# 780-00057_rev1_Pg2_SCH_NRES_Crate_Slot_M.net
KiCad netlist of a schematic drawn in Altium Designer
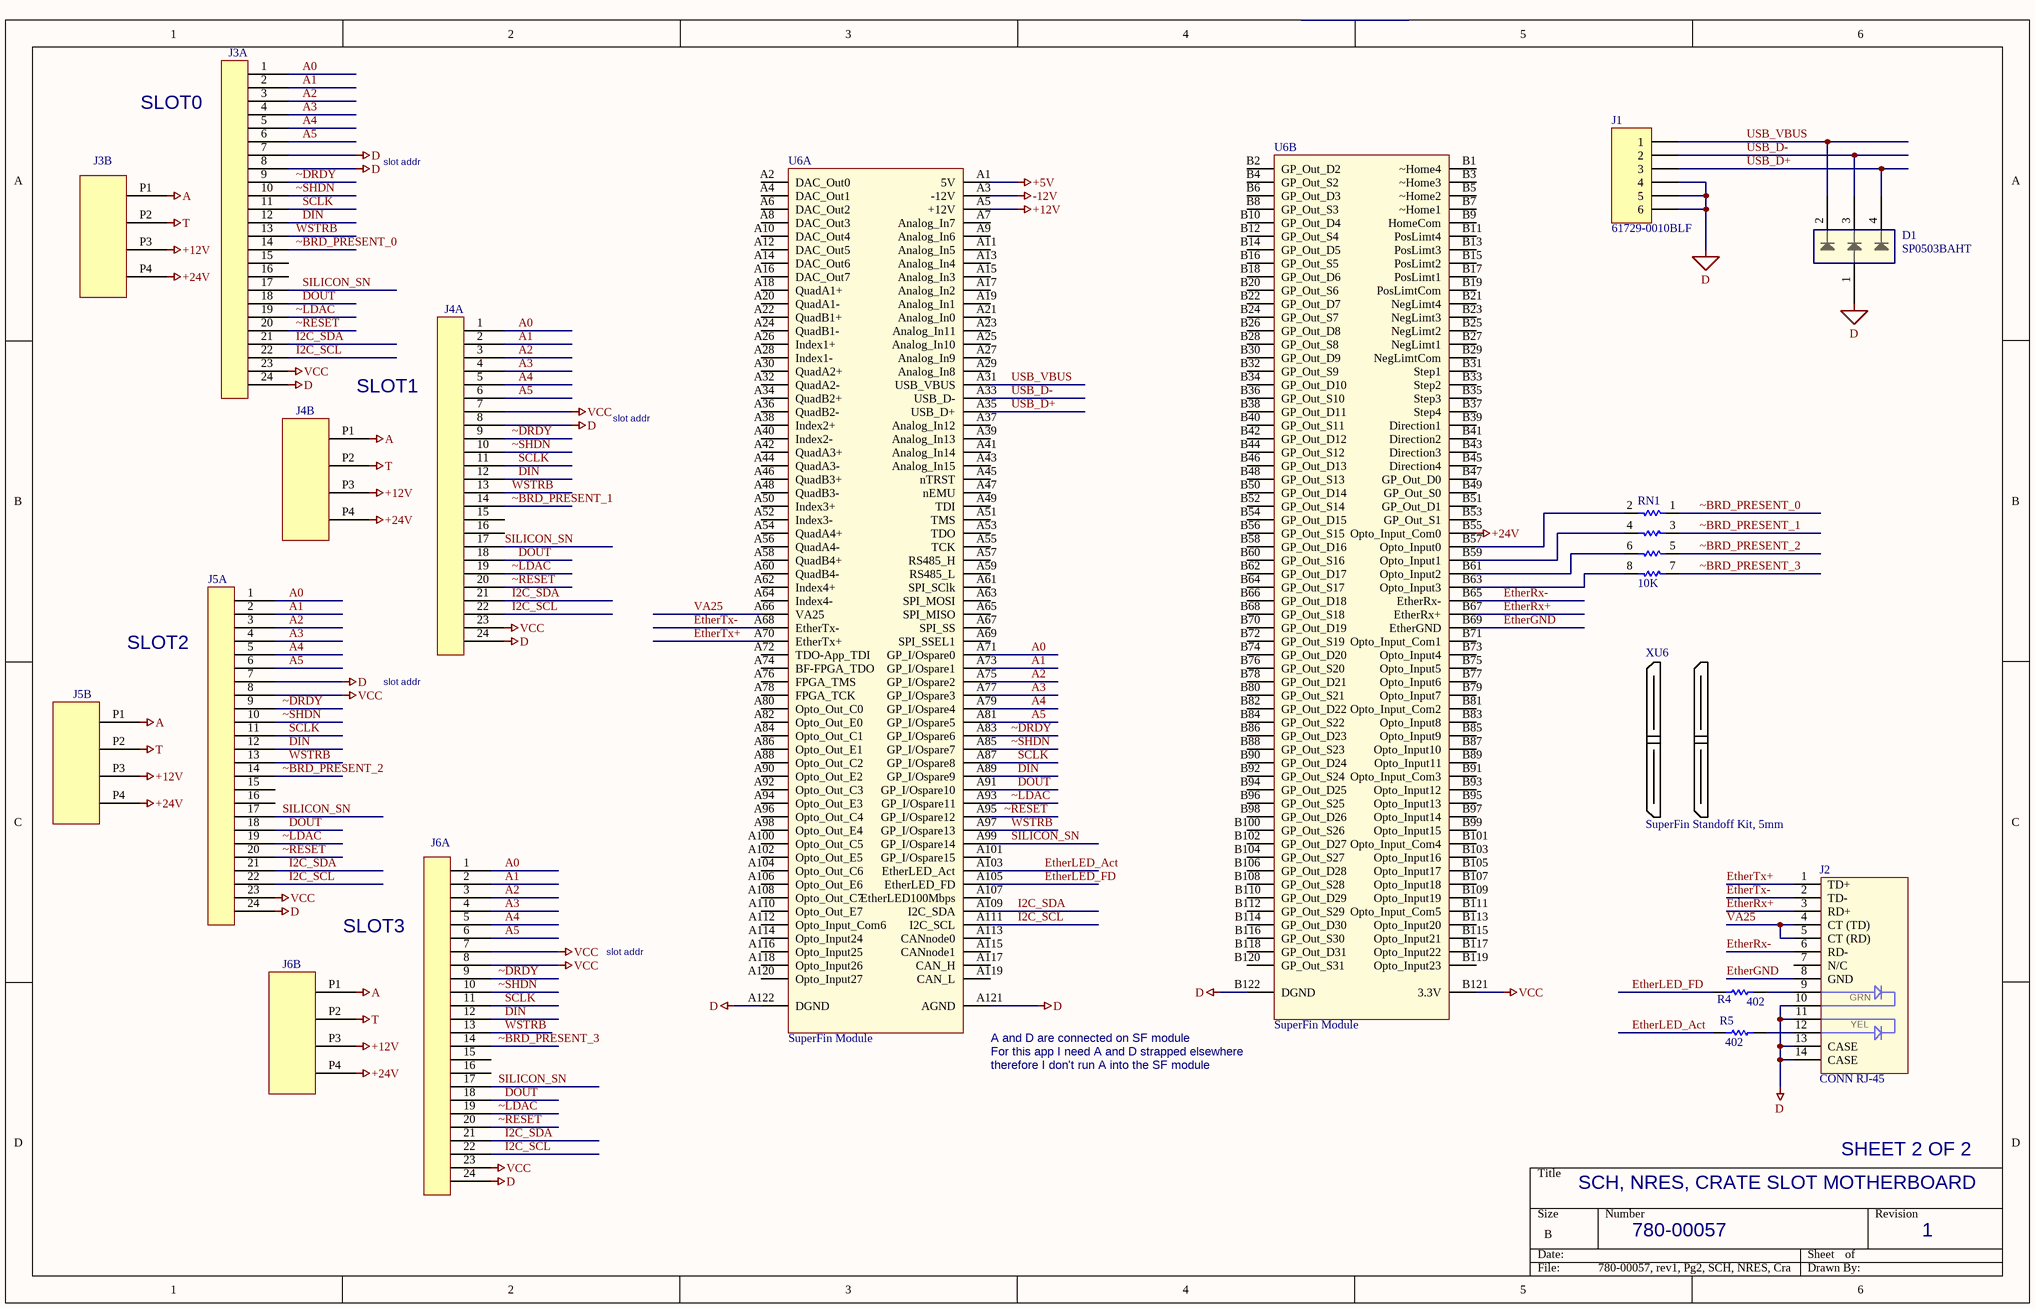
[diagram p0: 780-00057, rev1, Pg2, SCH, NRES, Crate Slot MotherBoard.SchDoc]

(export (version "E")
  (design (tool "Eeschema 10.0.6"))
  (components
    (comp (ref "D1")
      (value "SP0503BAHT")
      (footprint "SOT-143")
      (fields (field (name "MANUFACTURER") "LITTLEFUSE"))
      (libsource (lib "DJAHNG_Library_1") (part "3-Zener"))
    )
    (comp (ref "J1")
      (value "61729-0010BLF")
      (footprint "USB Vertical PCB")
      (description "Header, 6-Pin")
      (fields (field (name "MANUFACTURER") "FCI"))
      (libsource (lib "Miscellaneous Connectors") (part "Header 6"))
    )
    (comp (ref "J2")
      (value "CONN RJ-45")
      (footprint "RJ-45 w/magnetics")
      (description "Right Angle, Standard Profile, RJ45-Keyed, Flange Mount PCB Jack")
      (libsource (lib "Richs Schematic Components") (part "CONN RJ-45 with Magnetics"))
    )
    (comp (ref "J3")
      (value "Molex 46114 backplane connector, 24 signal, 4 pwr")
      (footprint "MOLEX 46114 SERIES")
      (libsource (lib "Richs Schematic Components") (part "Molex 46114 backplane connector, 24 signal, 4 pwr"))
    )
    (comp (ref "J4")
      (value "Molex 46114 backplane connector, 24 signal, 4 pwr")
      (footprint "MOLEX 46114 SERIES")
      (libsource (lib "Richs Schematic Components") (part "Molex 46114 backplane connector, 24 signal, 4 pwr"))
    )
    (comp (ref "J5")
      (value "Molex 46114 backplane connector, 24 signal, 4 pwr")
      (footprint "MOLEX 46114 SERIES")
      (libsource (lib "Richs Schematic Components") (part "Molex 46114 backplane connector, 24 signal, 4 pwr"))
    )
    (comp (ref "J6")
      (value "Molex 46114 backplane connector, 24 signal, 4 pwr")
      (footprint "MOLEX 46114 SERIES")
      (libsource (lib "Richs Schematic Components") (part "Molex 46114 backplane connector, 24 signal, 4 pwr"))
    )
    (comp (ref "R4")
      (value "402")
      (footprint "SMD_0805")
      (description "Resistor 0805")
      (fields (field (name "MANUFACTURER") "Vishay/Dale") (field (name "Comment") "Res 0805"))
      (libsource (lib "Richs Schematic Components") (part "Res SMD"))
    )
    (comp (ref "R5")
      (value "402")
      (footprint "SMD_0805")
      (description "Resistor 0805")
      (fields (field (name "MANUFACTURER") "Vishay/Dale") (field (name "Comment") "Res 0805"))
      (libsource (lib "Richs Schematic Components") (part "Res SMD"))
    )
    (comp (ref "RN1")
      (value "10K")
      (footprint "RES ARRAY 0603 x 4")
      (description "Resistor Array 4 Isolated")
      (fields (field (name "MANUFACTURER") "PANASONIC - ECG") (field (name "Comment") "RES ARRAY  x4 10K"))
      (libsource (lib "Richs Schematic Components") (part "RES ARRAY  x4 10K"))
    )
    (comp (ref "U6")
      (value "SuperFin Module")
      (footprint "SuperFin Footprint")
      (libsource (lib "Richs Schematic Components") (part "SuperFin Module"))
    )
    (comp (ref "XU6")
      (value "SuperFin Standoff Kit, 5mm")
      (libsource (lib "Richs Schematic Components") (part "SuperFin Standoff Kit, 5mm"))
    )
  )
  (nets
    (net (code "1") (name "+5V") (class "Default")
      (node (ref "U6") (pin "A1") (pinfunction "5V_A1") (pintype "passive"))
    )
    (net (code "2") (name "+12V") (class "Default")
      (node (ref "J3") (pin "P3") (pinfunction "S27_P3") (pintype "passive"))
      (node (ref "J4") (pin "P3") (pinfunction "S27_P3") (pintype "passive"))
      (node (ref "J5") (pin "P3") (pinfunction "S27_P3") (pintype "passive"))
      (node (ref "J6") (pin "P3") (pinfunction "S27_P3") (pintype "passive"))
      (node (ref "U6") (pin "A5") (pinfunction "+12V_A5") (pintype "passive"))
    )
    (net (code "3") (name "+24V") (class "Default")
      (node (ref "J3") (pin "P4") (pinfunction "S28_P4") (pintype "passive"))
      (node (ref "J4") (pin "P4") (pinfunction "S28_P4") (pintype "passive"))
      (node (ref "J5") (pin "P4") (pinfunction "S28_P4") (pintype "passive"))
      (node (ref "J6") (pin "P4") (pinfunction "S28_P4") (pintype "passive"))
      (node (ref "U6") (pin "B55") (pinfunction "Opto_Input_Com0_B55") (pintype "passive"))
    )
    (net (code "4") (name "-12V") (class "Default")
      (node (ref "U6") (pin "A3") (pinfunction "-12V_A3") (pintype "passive"))
    )
    (net (code "5") (name "/A0") (class "Default")
      (node (ref "J3") (pin "1") (pintype "passive"))
      (node (ref "J4") (pin "1") (pintype "passive"))
      (node (ref "J5") (pin "1") (pintype "passive"))
      (node (ref "J6") (pin "1") (pintype "passive"))
      (node (ref "U6") (pin "A71") (pinfunction "GP_I/Ospare0_A71") (pintype "passive"))
    )
    (net (code "6") (name "/A1") (class "Default")
      (node (ref "J3") (pin "2") (pintype "passive"))
      (node (ref "J4") (pin "2") (pintype "passive"))
      (node (ref "J5") (pin "2") (pintype "passive"))
      (node (ref "J6") (pin "2") (pintype "passive"))
      (node (ref "U6") (pin "A73") (pinfunction "GP_I/Ospare1_A73") (pintype "passive"))
    )
    (net (code "7") (name "/A2") (class "Default")
      (node (ref "J3") (pin "3") (pintype "passive"))
      (node (ref "J4") (pin "3") (pintype "passive"))
      (node (ref "J5") (pin "3") (pintype "passive"))
      (node (ref "J6") (pin "3") (pintype "passive"))
      (node (ref "U6") (pin "A75") (pinfunction "GP_I/Ospare2_A75") (pintype "passive"))
    )
    (net (code "8") (name "/A3") (class "Default")
      (node (ref "J3") (pin "4") (pintype "passive"))
      (node (ref "J4") (pin "4") (pintype "passive"))
      (node (ref "J5") (pin "4") (pintype "passive"))
      (node (ref "J6") (pin "4") (pintype "passive"))
      (node (ref "U6") (pin "A77") (pinfunction "GP_I/Ospare3_A77") (pintype "passive"))
    )
    (net (code "9") (name "/A4") (class "Default")
      (node (ref "J3") (pin "5") (pintype "passive"))
      (node (ref "J4") (pin "5") (pintype "passive"))
      (node (ref "J5") (pin "5") (pintype "passive"))
      (node (ref "J6") (pin "5") (pintype "passive"))
      (node (ref "U6") (pin "A79") (pinfunction "GP_I/Ospare4_A79") (pintype "passive"))
    )
    (net (code "10") (name "/A5") (class "Default")
      (node (ref "J3") (pin "6") (pintype "passive"))
      (node (ref "J4") (pin "6") (pintype "passive"))
      (node (ref "J5") (pin "6") (pintype "passive"))
      (node (ref "J6") (pin "6") (pintype "passive"))
      (node (ref "U6") (pin "A81") (pinfunction "GP_I/Ospare5_A81") (pintype "passive"))
    )
    (net (code "11") (name "/DIN") (class "Default")
      (node (ref "J3") (pin "12") (pintype "passive"))
      (node (ref "J4") (pin "12") (pintype "passive"))
      (node (ref "J5") (pin "12") (pintype "passive"))
      (node (ref "J6") (pin "12") (pintype "passive"))
      (node (ref "U6") (pin "A89") (pinfunction "GP_I/Ospare9_A89") (pintype "passive"))
    )
    (net (code "12") (name "/DOUT") (class "Default")
      (node (ref "J3") (pin "18") (pintype "passive"))
      (node (ref "J4") (pin "18") (pintype "passive"))
      (node (ref "J5") (pin "18") (pintype "passive"))
      (node (ref "J6") (pin "18") (pintype "passive"))
      (node (ref "U6") (pin "A91") (pinfunction "GP_I/Ospare10_A91") (pintype "passive"))
    )
    (net (code "13") (name "/EtherGND") (class "Default")
      (node (ref "J2") (pin "8") (pinfunction "GND_8") (pintype "passive"))
      (node (ref "U6") (pin "B69") (pinfunction "EtherGND_B69") (pintype "passive"))
    )
    (net (code "14") (name "/EtherLED_Act") (class "Default")
      (node (ref "R5") (pin "1") (pinfunction "1_1") (pintype "passive"))
      (node (ref "U6") (pin "A103") (pinfunction "EtherLED_Act_A103") (pintype "passive"))
    )
    (net (code "15") (name "/EtherLED_FD") (class "Default")
      (node (ref "R4") (pin "1") (pinfunction "1_1") (pintype "passive"))
      (node (ref "U6") (pin "A105") (pinfunction "EtherLED_FD_A105") (pintype "passive"))
    )
    (net (code "16") (name "/EtherRx+") (class "Default")
      (node (ref "J2") (pin "3") (pinfunction "RD+_3") (pintype "passive"))
      (node (ref "U6") (pin "B67") (pinfunction "EtherRx+_B67") (pintype "passive"))
    )
    (net (code "17") (name "/EtherRx-") (class "Default")
      (node (ref "J2") (pin "6") (pinfunction "RD-_6") (pintype "passive"))
      (node (ref "U6") (pin "B65") (pinfunction "EtherRx-_B65") (pintype "passive"))
    )
    (net (code "18") (name "/EtherTx+") (class "Default")
      (node (ref "J2") (pin "1") (pinfunction "TD+_1") (pintype "passive"))
      (node (ref "U6") (pin "A70") (pinfunction "EtherTx+_A70") (pintype "passive"))
    )
    (net (code "19") (name "/EtherTx-") (class "Default")
      (node (ref "J2") (pin "2") (pinfunction "TD-_2") (pintype "passive"))
      (node (ref "U6") (pin "A68") (pinfunction "EtherTx-_A68") (pintype "passive"))
    )
    (net (code "20") (name "/I2C_SCL") (class "Default")
      (node (ref "J3") (pin "22") (pintype "passive"))
      (node (ref "J4") (pin "22") (pintype "passive"))
      (node (ref "J5") (pin "22") (pintype "passive"))
      (node (ref "J6") (pin "22") (pintype "passive"))
      (node (ref "U6") (pin "A111") (pinfunction "I2C_SCL_A111") (pintype "passive"))
    )
    (net (code "21") (name "/I2C_SDA") (class "Default")
      (node (ref "J3") (pin "21") (pintype "passive"))
      (node (ref "J4") (pin "21") (pintype "passive"))
      (node (ref "J5") (pin "21") (pintype "passive"))
      (node (ref "J6") (pin "21") (pintype "passive"))
      (node (ref "U6") (pin "A109") (pinfunction "I2C_SDA_A109") (pintype "passive"))
    )
    (net (code "22") (name "/SCLK") (class "Default")
      (node (ref "J3") (pin "11") (pintype "passive"))
      (node (ref "J4") (pin "11") (pintype "passive"))
      (node (ref "J5") (pin "11") (pintype "passive"))
      (node (ref "J6") (pin "11") (pintype "passive"))
      (node (ref "U6") (pin "A87") (pinfunction "GP_I/Ospare8_A87") (pintype "passive"))
    )
    (net (code "23") (name "/SILICON_SN") (class "Default")
      (node (ref "J3") (pin "17") (pintype "passive"))
      (node (ref "J4") (pin "17") (pintype "passive"))
      (node (ref "J5") (pin "17") (pintype "passive"))
      (node (ref "J6") (pin "17") (pintype "passive"))
      (node (ref "U6") (pin "A99") (pinfunction "GP_I/Ospare14_A99") (pintype "passive"))
    )
    (net (code "24") (name "/USB_D+") (class "Default")
      (node (ref "D1") (pin "4") (pinfunction "K3_4") (pintype "passive"))
      (node (ref "J1") (pin "3") (pinfunction "3_3") (pintype "passive"))
      (node (ref "U6") (pin "A35") (pinfunction "USB_D+_A35") (pintype "passive"))
    )
    (net (code "25") (name "/USB_D-") (class "Default")
      (node (ref "D1") (pin "3") (pinfunction "K2_3") (pintype "passive"))
      (node (ref "J1") (pin "2") (pinfunction "2_2") (pintype "passive"))
      (node (ref "U6") (pin "A33") (pinfunction "USB_D-_A33") (pintype "passive"))
    )
    (net (code "26") (name "/USB_VBUS") (class "Default")
      (node (ref "D1") (pin "2") (pinfunction "K1_2") (pintype "passive"))
      (node (ref "J1") (pin "1") (pinfunction "1_1") (pintype "passive"))
      (node (ref "U6") (pin "A31") (pinfunction "USB_VBUS_A31") (pintype "passive"))
    )
    (net (code "27") (name "/VA25") (class "Default")
      (node (ref "J2") (pin "4") (pinfunction "CT_(TD)_4") (pintype "passive"))
      (node (ref "J2") (pin "5") (pinfunction "CT_(RD)_5") (pintype "passive"))
      (node (ref "U6") (pin "A66") (pinfunction "VA25_A66") (pintype "passive"))
    )
    (net (code "28") (name "/WSTRB") (class "Default")
      (node (ref "J3") (pin "13") (pintype "passive"))
      (node (ref "J4") (pin "13") (pintype "passive"))
      (node (ref "J5") (pin "13") (pintype "passive"))
      (node (ref "J6") (pin "13") (pintype "passive"))
      (node (ref "U6") (pin "A97") (pinfunction "GP_I/Ospare13_A97") (pintype "passive"))
    )
    (net (code "29") (name "/~BRD_PRESENT_0") (class "Default")
      (node (ref "J3") (pin "14") (pintype "passive"))
      (node (ref "RN1") (pin "1") (pinfunction "1_1") (pintype "passive"))
    )
    (net (code "30") (name "/~BRD_PRESENT_1") (class "Default")
      (node (ref "J4") (pin "14") (pintype "passive"))
      (node (ref "RN1") (pin "3") (pinfunction "3_3") (pintype "passive"))
    )
    (net (code "31") (name "/~BRD_PRESENT_2") (class "Default")
      (node (ref "J5") (pin "14") (pintype "passive"))
      (node (ref "RN1") (pin "5") (pinfunction "5_5") (pintype "passive"))
    )
    (net (code "32") (name "/~BRD_PRESENT_3") (class "Default")
      (node (ref "J6") (pin "14") (pintype "passive"))
      (node (ref "RN1") (pin "7") (pinfunction "1_7") (pintype "passive"))
    )
    (net (code "33") (name "/~DRDY") (class "Default")
      (node (ref "J3") (pin "9") (pintype "passive"))
      (node (ref "J4") (pin "9") (pintype "passive"))
      (node (ref "J5") (pin "9") (pintype "passive"))
      (node (ref "J6") (pin "9") (pintype "passive"))
      (node (ref "U6") (pin "A83") (pinfunction "GP_I/Ospare6_A83") (pintype "passive"))
    )
    (net (code "34") (name "/~LDAC") (class "Default")
      (node (ref "J3") (pin "19") (pintype "passive"))
      (node (ref "J4") (pin "19") (pintype "passive"))
      (node (ref "J5") (pin "19") (pintype "passive"))
      (node (ref "J6") (pin "19") (pintype "passive"))
      (node (ref "U6") (pin "A93") (pinfunction "GP_I/Ospare11_A93") (pintype "passive"))
    )
    (net (code "35") (name "/~RESET") (class "Default")
      (node (ref "J3") (pin "20") (pintype "passive"))
      (node (ref "J4") (pin "20") (pintype "passive"))
      (node (ref "J5") (pin "20") (pintype "passive"))
      (node (ref "J6") (pin "20") (pintype "passive"))
      (node (ref "U6") (pin "A95") (pinfunction "GP_I/Ospare12_A95") (pintype "passive"))
    )
    (net (code "36") (name "/~SHDN") (class "Default")
      (node (ref "J3") (pin "10") (pintype "passive"))
      (node (ref "J4") (pin "10") (pintype "passive"))
      (node (ref "J5") (pin "10") (pintype "passive"))
      (node (ref "J6") (pin "10") (pintype "passive"))
      (node (ref "U6") (pin "A85") (pinfunction "GP_I/Ospare7_A85") (pintype "passive"))
    )
    (net (code "37") (name "A") (class "Default")
      (node (ref "J3") (pin "P1") (pinfunction "S25_P1") (pintype "passive"))
      (node (ref "J4") (pin "P1") (pinfunction "S25_P1") (pintype "passive"))
      (node (ref "J5") (pin "P1") (pinfunction "S25_P1") (pintype "passive"))
      (node (ref "J6") (pin "P1") (pinfunction "S25_P1") (pintype "passive"))
    )
    (net (code "38") (name "D") (class "Default")
      (node (ref "D1") (pin "1") (pinfunction "A_1") (pintype "passive"))
      (node (ref "J1") (pin "4") (pinfunction "4_4") (pintype "passive"))
      (node (ref "J1") (pin "5") (pinfunction "5_5") (pintype "passive"))
      (node (ref "J1") (pin "6") (pinfunction "6_6") (pintype "passive"))
      (node (ref "J2") (pin "10") (pinfunction "GRN-Cathode_10") (pintype "passive"))
      (node (ref "J2") (pin "11") (pinfunction "YEL-Cathode_11") (pintype "passive"))
      (node (ref "J2") (pin "13") (pinfunction "CASE_13") (pintype "passive"))
      (node (ref "J2") (pin "14") (pinfunction "CASE_14") (pintype "passive"))
      (node (ref "J3") (pin "24") (pintype "passive"))
      (node (ref "J3") (pin "7") (pintype "passive"))
      (node (ref "J3") (pin "8") (pintype "passive"))
      (node (ref "J4") (pin "24") (pintype "passive"))
      (node (ref "J4") (pin "8") (pintype "passive"))
      (node (ref "J5") (pin "24") (pintype "passive"))
      (node (ref "J5") (pin "7") (pintype "passive"))
      (node (ref "J6") (pin "24") (pintype "passive"))
      (node (ref "U6") (pin "A121") (pinfunction "AGND_A121") (pintype "passive"))
      (node (ref "U6") (pin "A122") (pinfunction "DGND_A122") (pintype "passive"))
      (node (ref "U6") (pin "B122") (pinfunction "DGND_B122") (pintype "passive"))
    )
    (net (code "39") (name "Net-(J2-GRN-Anode)") (class "Default")
      (node (ref "J2") (pin "9") (pinfunction "GRN-Anode_9") (pintype "passive"))
      (node (ref "R4") (pin "2") (pinfunction "2_2") (pintype "passive"))
    )
    (net (code "40") (name "Net-(J2-YEL-Anode)") (class "Default")
      (node (ref "J2") (pin "12") (pinfunction "YEL-Anode_12") (pintype "passive"))
      (node (ref "R5") (pin "2") (pinfunction "2_2") (pintype "passive"))
    )
    (net (code "41") (name "Net-(U6B-Opto_Input0)") (class "Default")
      (node (ref "RN1") (pin "2") (pinfunction "2_2") (pintype "passive"))
      (node (ref "U6") (pin "B57") (pinfunction "Opto_Input0_B57") (pintype "passive"))
    )
    (net (code "42") (name "Net-(U6B-Opto_Input1)") (class "Default")
      (node (ref "RN1") (pin "4") (pinfunction "4_4") (pintype "passive"))
      (node (ref "U6") (pin "B59") (pinfunction "Opto_Input1_B59") (pintype "passive"))
    )
    (net (code "43") (name "Net-(U6B-Opto_Input2)") (class "Default")
      (node (ref "RN1") (pin "6") (pinfunction "6_6") (pintype "passive"))
      (node (ref "U6") (pin "B61") (pinfunction "Opto_Input2_B61") (pintype "passive"))
    )
    (net (code "44") (name "Net-(U6B-Opto_Input3)") (class "Default")
      (node (ref "RN1") (pin "8") (pinfunction "8_8") (pintype "passive"))
      (node (ref "U6") (pin "B63") (pinfunction "Opto_Input3_B63") (pintype "passive"))
    )
    (net (code "45") (name "T") (class "Default")
      (node (ref "J3") (pin "P2") (pinfunction "S26_P2") (pintype "passive"))
      (node (ref "J4") (pin "P2") (pinfunction "S26_P2") (pintype "passive"))
      (node (ref "J5") (pin "P2") (pinfunction "S26_P2") (pintype "passive"))
      (node (ref "J6") (pin "P2") (pinfunction "S26_P2") (pintype "passive"))
    )
    (net (code "46") (name "VCC") (class "Default")
      (node (ref "J3") (pin "23") (pintype "passive"))
      (node (ref "J4") (pin "23") (pintype "passive"))
      (node (ref "J4") (pin "7") (pintype "passive"))
      (node (ref "J5") (pin "23") (pintype "passive"))
      (node (ref "J5") (pin "8") (pintype "passive"))
      (node (ref "J6") (pin "23") (pintype "passive"))
      (node (ref "J6") (pin "7") (pintype "passive"))
      (node (ref "J6") (pin "8") (pintype "passive"))
      (node (ref "U6") (pin "B121") (pinfunction "3.3V_B121") (pintype "passive"))
    )
    (net (code "47") (name "unconnected-(J2-N{slash}C-Pad7)") (class "Default")
      (node (ref "J2") (pin "7") (pinfunction "N/C_7") (pintype "passive"))
    )
    (net (code "48") (name "unconnected-(J3-Pad15)") (class "Default")
      (node (ref "J3") (pin "15") (pintype "passive"))
    )
    (net (code "49") (name "unconnected-(J3-Pad16)") (class "Default")
      (node (ref "J3") (pin "16") (pintype "passive"))
    )
    (net (code "50") (name "unconnected-(J4-Pad15)") (class "Default")
      (node (ref "J4") (pin "15") (pintype "passive"))
    )
    (net (code "51") (name "unconnected-(J4-Pad16)") (class "Default")
      (node (ref "J4") (pin "16") (pintype "passive"))
    )
    (net (code "52") (name "unconnected-(J5-Pad15)") (class "Default")
      (node (ref "J5") (pin "15") (pintype "passive"))
    )
    (net (code "53") (name "unconnected-(J5-Pad16)") (class "Default")
      (node (ref "J5") (pin "16") (pintype "passive"))
    )
    (net (code "54") (name "unconnected-(J6-Pad15)") (class "Default")
      (node (ref "J6") (pin "15") (pintype "passive"))
    )
    (net (code "55") (name "unconnected-(J6-Pad16)") (class "Default")
      (node (ref "J6") (pin "16") (pintype "passive"))
    )
    (net (code "56") (name "unconnected-(U6A-Analog_In0-PadA21)") (class "Default")
      (node (ref "U6") (pin "A21") (pinfunction "Analog_In0_A21") (pintype "passive"))
    )
    (net (code "57") (name "unconnected-(U6A-Analog_In1-PadA19)") (class "Default")
      (node (ref "U6") (pin "A19") (pinfunction "Analog_In1_A19") (pintype "passive"))
    )
    (net (code "58") (name "unconnected-(U6A-Analog_In2-PadA17)") (class "Default")
      (node (ref "U6") (pin "A17") (pinfunction "Analog_In2_A17") (pintype "passive"))
    )
    (net (code "59") (name "unconnected-(U6A-Analog_In3-PadA15)") (class "Default")
      (node (ref "U6") (pin "A15") (pinfunction "Analog_In3_A15") (pintype "passive"))
    )
    (net (code "60") (name "unconnected-(U6A-Analog_In4-PadA13)") (class "Default")
      (node (ref "U6") (pin "A13") (pinfunction "Analog_In4_A13") (pintype "passive"))
    )
    (net (code "61") (name "unconnected-(U6A-Analog_In5-PadA11)") (class "Default")
      (node (ref "U6") (pin "A11") (pinfunction "Analog_In5_A11") (pintype "passive"))
    )
    (net (code "62") (name "unconnected-(U6A-Analog_In6-PadA9)") (class "Default")
      (node (ref "U6") (pin "A9") (pinfunction "Analog_In6_A9") (pintype "passive"))
    )
    (net (code "63") (name "unconnected-(U6A-Analog_In7-PadA7)") (class "Default")
      (node (ref "U6") (pin "A7") (pinfunction "Analog_In7_A7") (pintype "passive"))
    )
    (net (code "64") (name "unconnected-(U6A-Analog_In8-PadA29)") (class "Default")
      (node (ref "U6") (pin "A29") (pinfunction "Analog_In8_A29") (pintype "passive"))
    )
    (net (code "65") (name "unconnected-(U6A-Analog_In9-PadA27)") (class "Default")
      (node (ref "U6") (pin "A27") (pinfunction "Analog_In9_A27") (pintype "passive"))
    )
    (net (code "66") (name "unconnected-(U6A-Analog_In10-PadA25)") (class "Default")
      (node (ref "U6") (pin "A25") (pinfunction "Analog_In10_A25") (pintype "passive"))
    )
    (net (code "67") (name "unconnected-(U6A-Analog_In11-PadA23)") (class "Default")
      (node (ref "U6") (pin "A23") (pinfunction "Analog_In11_A23") (pintype "passive"))
    )
    (net (code "68") (name "unconnected-(U6A-Analog_In12-PadA37)") (class "Default")
      (node (ref "U6") (pin "A37") (pinfunction "Analog_In12_A37") (pintype "passive"))
    )
    (net (code "69") (name "unconnected-(U6A-Analog_In13-PadA39)") (class "Default")
      (node (ref "U6") (pin "A39") (pinfunction "Analog_In13_A39") (pintype "passive"))
    )
    (net (code "70") (name "unconnected-(U6A-Analog_In14-PadA41)") (class "Default")
      (node (ref "U6") (pin "A41") (pinfunction "Analog_In14_A41") (pintype "passive"))
    )
    (net (code "71") (name "unconnected-(U6A-Analog_In15-PadA43)") (class "Default")
      (node (ref "U6") (pin "A43") (pinfunction "Analog_In15_A43") (pintype "passive"))
    )
    (net (code "72") (name "unconnected-(U6A-BF-FPGA_TDO-PadA74)") (class "Default")
      (node (ref "U6") (pin "A74") (pinfunction "BF-FPGA_TDO_A74") (pintype "passive"))
    )
    (net (code "73") (name "unconnected-(U6A-CAN_H-PadA117)") (class "Default")
      (node (ref "U6") (pin "A117") (pinfunction "CAN_H_A117") (pintype "passive"))
    )
    (net (code "74") (name "unconnected-(U6A-CAN_L-PadA119)") (class "Default")
      (node (ref "U6") (pin "A119") (pinfunction "CAN_L_A119") (pintype "passive"))
    )
    (net (code "75") (name "unconnected-(U6A-CANnode0-PadA113)") (class "Default")
      (node (ref "U6") (pin "A113") (pinfunction "CANnode0_A113") (pintype "passive"))
    )
    (net (code "76") (name "unconnected-(U6A-CANnode1-PadA115)") (class "Default")
      (node (ref "U6") (pin "A115") (pinfunction "CANnode1_A115") (pintype "passive"))
    )
    (net (code "77") (name "unconnected-(U6A-DAC_Out0-PadA2)") (class "Default")
      (node (ref "U6") (pin "A2") (pinfunction "DAC_Out0_A2") (pintype "passive"))
    )
    (net (code "78") (name "unconnected-(U6A-DAC_Out1-PadA4)") (class "Default")
      (node (ref "U6") (pin "A4") (pinfunction "DAC_Out1_A4") (pintype "passive"))
    )
    (net (code "79") (name "unconnected-(U6A-DAC_Out2-PadA6)") (class "Default")
      (node (ref "U6") (pin "A6") (pinfunction "DAC_Out2_A6") (pintype "passive"))
    )
    (net (code "80") (name "unconnected-(U6A-DAC_Out3-PadA8)") (class "Default")
      (node (ref "U6") (pin "A8") (pinfunction "DAC_Out3_A8") (pintype "passive"))
    )
    (net (code "81") (name "unconnected-(U6A-DAC_Out4-PadA10)") (class "Default")
      (node (ref "U6") (pin "A10") (pinfunction "DAC_Out4_A10") (pintype "passive"))
    )
    (net (code "82") (name "unconnected-(U6A-DAC_Out5-PadA12)") (class "Default")
      (node (ref "U6") (pin "A12") (pinfunction "DAC_Out5_A12") (pintype "passive"))
    )
    (net (code "83") (name "unconnected-(U6A-DAC_Out6-PadA14)") (class "Default")
      (node (ref "U6") (pin "A14") (pinfunction "DAC_Out6_A14") (pintype "passive"))
    )
    (net (code "84") (name "unconnected-(U6A-DAC_Out7-PadA16)") (class "Default")
      (node (ref "U6") (pin "A16") (pinfunction "DAC_Out7_A16") (pintype "passive"))
    )
    (net (code "85") (name "unconnected-(U6A-EtherLED100Mbps-PadA107)") (class "Default")
      (node (ref "U6") (pin "A107") (pinfunction "EtherLED100Mbps_A107") (pintype "passive"))
    )
    (net (code "86") (name "unconnected-(U6A-FPGA_TCK-PadA78)") (class "Default")
      (node (ref "U6") (pin "A78") (pinfunction "FPGA_TCK_A78") (pintype "passive"))
    )
    (net (code "87") (name "unconnected-(U6A-FPGA_TMS-PadA76)") (class "Default")
      (node (ref "U6") (pin "A76") (pinfunction "FPGA_TMS_A76") (pintype "passive"))
    )
    (net (code "88") (name "unconnected-(U6A-GP_I{slash}Ospare15-PadA101)") (class "Default")
      (node (ref "U6") (pin "A101") (pinfunction "GP_I/Ospare15_A101") (pintype "passive"))
    )
    (net (code "89") (name "unconnected-(U6A-Index1+-PadA26)") (class "Default")
      (node (ref "U6") (pin "A26") (pinfunction "Index1+_A26") (pintype "passive"))
    )
    (net (code "90") (name "unconnected-(U6A-Index1--PadA28)") (class "Default")
      (node (ref "U6") (pin "A28") (pinfunction "Index1-_A28") (pintype "passive"))
    )
    (net (code "91") (name "unconnected-(U6A-Index2+-PadA38)") (class "Default")
      (node (ref "U6") (pin "A38") (pinfunction "Index2+_A38") (pintype "passive"))
    )
    (net (code "92") (name "unconnected-(U6A-Index2--PadA40)") (class "Default")
      (node (ref "U6") (pin "A40") (pinfunction "Index2-_A40") (pintype "passive"))
    )
    (net (code "93") (name "unconnected-(U6A-Index3+-PadA50)") (class "Default")
      (node (ref "U6") (pin "A50") (pinfunction "Index3+_A50") (pintype "passive"))
    )
    (net (code "94") (name "unconnected-(U6A-Index3--PadA52)") (class "Default")
      (node (ref "U6") (pin "A52") (pinfunction "Index3-_A52") (pintype "passive"))
    )
    (net (code "95") (name "unconnected-(U6A-Index4+-PadA62)") (class "Default")
      (node (ref "U6") (pin "A62") (pinfunction "Index4+_A62") (pintype "passive"))
    )
    (net (code "96") (name "unconnected-(U6A-Index4--PadA64)") (class "Default")
      (node (ref "U6") (pin "A64") (pinfunction "Index4-_A64") (pintype "passive"))
    )
    (net (code "97") (name "unconnected-(U6A-Opto_Input24-PadA114)") (class "Default")
      (node (ref "U6") (pin "A114") (pinfunction "Opto_Input24_A114") (pintype "passive"))
    )
    (net (code "98") (name "unconnected-(U6A-Opto_Input25-PadA116)") (class "Default")
      (node (ref "U6") (pin "A116") (pinfunction "Opto_Input25_A116") (pintype "passive"))
    )
    (net (code "99") (name "unconnected-(U6A-Opto_Input26-PadA118)") (class "Default")
      (node (ref "U6") (pin "A118") (pinfunction "Opto_Input26_A118") (pintype "passive"))
    )
    (net (code "100") (name "unconnected-(U6A-Opto_Input27-PadA120)") (class "Default")
      (node (ref "U6") (pin "A120") (pinfunction "Opto_Input27_A120") (pintype "passive"))
    )
    (net (code "101") (name "unconnected-(U6A-Opto_Input_Com6-PadA112)") (class "Default")
      (node (ref "U6") (pin "A112") (pinfunction "Opto_Input_Com6_A112") (pintype "passive"))
    )
    (net (code "102") (name "unconnected-(U6A-Opto_Out_C0-PadA80)") (class "Default")
      (node (ref "U6") (pin "A80") (pinfunction "Opto_Out_C0_A80") (pintype "passive"))
    )
    (net (code "103") (name "unconnected-(U6A-Opto_Out_C1-PadA84)") (class "Default")
      (node (ref "U6") (pin "A84") (pinfunction "Opto_Out_C1_A84") (pintype "passive"))
    )
    (net (code "104") (name "unconnected-(U6A-Opto_Out_C2-PadA88)") (class "Default")
      (node (ref "U6") (pin "A88") (pinfunction "Opto_Out_C2_A88") (pintype "passive"))
    )
    (net (code "105") (name "unconnected-(U6A-Opto_Out_C3-PadA92)") (class "Default")
      (node (ref "U6") (pin "A92") (pinfunction "Opto_Out_C3_A92") (pintype "passive"))
    )
    (net (code "106") (name "unconnected-(U6A-Opto_Out_C4-PadA96)") (class "Default")
      (node (ref "U6") (pin "A96") (pinfunction "Opto_Out_C4_A96") (pintype "passive"))
    )
    (net (code "107") (name "unconnected-(U6A-Opto_Out_C5-PadA100)") (class "Default")
      (node (ref "U6") (pin "A100") (pinfunction "Opto_Out_C5_A100") (pintype "passive"))
    )
    (net (code "108") (name "unconnected-(U6A-Opto_Out_C6-PadA104)") (class "Default")
      (node (ref "U6") (pin "A104") (pinfunction "Opto_Out_C6_A104") (pintype "passive"))
    )
    (net (code "109") (name "unconnected-(U6A-Opto_Out_C7-PadA108)") (class "Default")
      (node (ref "U6") (pin "A108") (pinfunction "Opto_Out_C7_A108") (pintype "passive"))
    )
    (net (code "110") (name "unconnected-(U6A-Opto_Out_E0-PadA82)") (class "Default")
      (node (ref "U6") (pin "A82") (pinfunction "Opto_Out_E0_A82") (pintype "passive"))
    )
    (net (code "111") (name "unconnected-(U6A-Opto_Out_E1-PadA86)") (class "Default")
      (node (ref "U6") (pin "A86") (pinfunction "Opto_Out_E1_A86") (pintype "passive"))
    )
    (net (code "112") (name "unconnected-(U6A-Opto_Out_E2-PadA90)") (class "Default")
      (node (ref "U6") (pin "A90") (pinfunction "Opto_Out_E2_A90") (pintype "passive"))
    )
    (net (code "113") (name "unconnected-(U6A-Opto_Out_E3-PadA94)") (class "Default")
      (node (ref "U6") (pin "A94") (pinfunction "Opto_Out_E3_A94") (pintype "passive"))
    )
    (net (code "114") (name "unconnected-(U6A-Opto_Out_E4-PadA98)") (class "Default")
      (node (ref "U6") (pin "A98") (pinfunction "Opto_Out_E4_A98") (pintype "passive"))
    )
    (net (code "115") (name "unconnected-(U6A-Opto_Out_E5-PadA102)") (class "Default")
      (node (ref "U6") (pin "A102") (pinfunction "Opto_Out_E5_A102") (pintype "passive"))
    )
    (net (code "116") (name "unconnected-(U6A-Opto_Out_E6-PadA106)") (class "Default")
      (node (ref "U6") (pin "A106") (pinfunction "Opto_Out_E6_A106") (pintype "passive"))
    )
    (net (code "117") (name "unconnected-(U6A-Opto_Out_E7-PadA110)") (class "Default")
      (node (ref "U6") (pin "A110") (pinfunction "Opto_Out_E7_A110") (pintype "passive"))
    )
    (net (code "118") (name "unconnected-(U6A-QuadA1+-PadA18)") (class "Default")
      (node (ref "U6") (pin "A18") (pinfunction "QuadA1+_A18") (pintype "passive"))
    )
    (net (code "119") (name "unconnected-(U6A-QuadA1--PadA20)") (class "Default")
      (node (ref "U6") (pin "A20") (pinfunction "QuadA1-_A20") (pintype "passive"))
    )
    (net (code "120") (name "unconnected-(U6A-QuadA2+-PadA30)") (class "Default")
      (node (ref "U6") (pin "A30") (pinfunction "QuadA2+_A30") (pintype "passive"))
    )
    (net (code "121") (name "unconnected-(U6A-QuadA2--PadA32)") (class "Default")
      (node (ref "U6") (pin "A32") (pinfunction "QuadA2-_A32") (pintype "passive"))
    )
    (net (code "122") (name "unconnected-(U6A-QuadA3+-PadA42)") (class "Default")
      (node (ref "U6") (pin "A42") (pinfunction "QuadA3+_A42") (pintype "passive"))
    )
    (net (code "123") (name "unconnected-(U6A-QuadA3--PadA44)") (class "Default")
      (node (ref "U6") (pin "A44") (pinfunction "QuadA3-_A44") (pintype "passive"))
    )
    (net (code "124") (name "unconnected-(U6A-QuadA4+-PadA54)") (class "Default")
      (node (ref "U6") (pin "A54") (pinfunction "QuadA4+_A54") (pintype "passive"))
    )
    (net (code "125") (name "unconnected-(U6A-QuadA4--PadA56)") (class "Default")
      (node (ref "U6") (pin "A56") (pinfunction "QuadA4-_A56") (pintype "passive"))
    )
    (net (code "126") (name "unconnected-(U6A-QuadB1+-PadA22)") (class "Default")
      (node (ref "U6") (pin "A22") (pinfunction "QuadB1+_A22") (pintype "passive"))
    )
    (net (code "127") (name "unconnected-(U6A-QuadB1--PadA24)") (class "Default")
      (node (ref "U6") (pin "A24") (pinfunction "QuadB1-_A24") (pintype "passive"))
    )
    (net (code "128") (name "unconnected-(U6A-QuadB2+-PadA34)") (class "Default")
      (node (ref "U6") (pin "A34") (pinfunction "QuadB2+_A34") (pintype "passive"))
    )
    (net (code "129") (name "unconnected-(U6A-QuadB2--PadA36)") (class "Default")
      (node (ref "U6") (pin "A36") (pinfunction "QuadB2-_A36") (pintype "passive"))
    )
    (net (code "130") (name "unconnected-(U6A-QuadB3+-PadA46)") (class "Default")
      (node (ref "U6") (pin "A46") (pinfunction "QuadB3+_A46") (pintype "passive"))
    )
    (net (code "131") (name "unconnected-(U6A-QuadB3--PadA48)") (class "Default")
      (node (ref "U6") (pin "A48") (pinfunction "QuadB3-_A48") (pintype "passive"))
    )
    (net (code "132") (name "unconnected-(U6A-QuadB4+-PadA58)") (class "Default")
      (node (ref "U6") (pin "A58") (pinfunction "QuadB4+_A58") (pintype "passive"))
    )
    (net (code "133") (name "unconnected-(U6A-QuadB4--PadA60)") (class "Default")
      (node (ref "U6") (pin "A60") (pinfunction "QuadB4-_A60") (pintype "passive"))
    )
    (net (code "134") (name "unconnected-(U6A-RS485_H-PadA57)") (class "Default")
      (node (ref "U6") (pin "A57") (pinfunction "RS485_H_A57") (pintype "passive"))
    )
    (net (code "135") (name "unconnected-(U6A-RS485_L-PadA59)") (class "Default")
      (node (ref "U6") (pin "A59") (pinfunction "RS485_L_A59") (pintype "passive"))
    )
    (net (code "136") (name "unconnected-(U6A-SPI_MISO-PadA65)") (class "Default")
      (node (ref "U6") (pin "A65") (pinfunction "SPI_MISO_A65") (pintype "passive"))
    )
    (net (code "137") (name "unconnected-(U6A-SPI_MOSI-PadA63)") (class "Default")
      (node (ref "U6") (pin "A63") (pinfunction "SPI_MOSI_A63") (pintype "passive"))
    )
    (net (code "138") (name "unconnected-(U6A-SPI_SClk-PadA61)") (class "Default")
      (node (ref "U6") (pin "A61") (pinfunction "SPI_SClk_A61") (pintype "passive"))
    )
    (net (code "139") (name "unconnected-(U6A-SPI_SS-PadA67)") (class "Default")
      (node (ref "U6") (pin "A67") (pinfunction "SPI_SS_A67") (pintype "passive"))
    )
    (net (code "140") (name "unconnected-(U6A-SPI_SSEL1-PadA69)") (class "Default")
      (node (ref "U6") (pin "A69") (pinfunction "SPI_SSEL1_A69") (pintype "passive"))
    )
    (net (code "141") (name "unconnected-(U6A-TCK-PadA55)") (class "Default")
      (node (ref "U6") (pin "A55") (pinfunction "TCK_A55") (pintype "passive"))
    )
    (net (code "142") (name "unconnected-(U6A-TDI-PadA49)") (class "Default")
      (node (ref "U6") (pin "A49") (pinfunction "TDI_A49") (pintype "passive"))
    )
    (net (code "143") (name "unconnected-(U6A-TDO-App_TDI-PadA72)") (class "Default")
      (node (ref "U6") (pin "A72") (pinfunction "TDO-App_TDI_A72") (pintype "passive"))
    )
    (net (code "144") (name "unconnected-(U6A-TDO-PadA53)") (class "Default")
      (node (ref "U6") (pin "A53") (pinfunction "TDO_A53") (pintype "passive"))
    )
    (net (code "145") (name "unconnected-(U6A-TMS-PadA51)") (class "Default")
      (node (ref "U6") (pin "A51") (pinfunction "TMS_A51") (pintype "passive"))
    )
    (net (code "146") (name "unconnected-(U6A-nEMU-PadA47)") (class "Default")
      (node (ref "U6") (pin "A47") (pinfunction "nEMU_A47") (pintype "passive"))
    )
    (net (code "147") (name "unconnected-(U6A-nTRST-PadA45)") (class "Default")
      (node (ref "U6") (pin "A45") (pinfunction "nTRST_A45") (pintype "passive"))
    )
    (net (code "148") (name "unconnected-(U6B-Direction1-PadB39)") (class "Default")
      (node (ref "U6") (pin "B39") (pinfunction "Direction1_B39") (pintype "passive"))
    )
    (net (code "149") (name "unconnected-(U6B-Direction2-PadB41)") (class "Default")
      (node (ref "U6") (pin "B41") (pinfunction "Direction2_B41") (pintype "passive"))
    )
    (net (code "150") (name "unconnected-(U6B-Direction3-PadB43)") (class "Default")
      (node (ref "U6") (pin "B43") (pinfunction "Direction3_B43") (pintype "passive"))
    )
    (net (code "151") (name "unconnected-(U6B-Direction4-PadB45)") (class "Default")
      (node (ref "U6") (pin "B45") (pinfunction "Direction4_B45") (pintype "passive"))
    )
    (net (code "152") (name "unconnected-(U6B-GP_Out_D0-PadB47)") (class "Default")
      (node (ref "U6") (pin "B47") (pinfunction "GP_Out_D0_B47") (pintype "passive"))
    )
    (net (code "153") (name "unconnected-(U6B-GP_Out_D1-PadB51)") (class "Default")
      (node (ref "U6") (pin "B51") (pinfunction "GP_Out_D1_B51") (pintype "passive"))
    )
    (net (code "154") (name "unconnected-(U6B-GP_Out_D2-PadB2)") (class "Default")
      (node (ref "U6") (pin "B2") (pinfunction "GP_Out_D2_B2") (pintype "passive"))
    )
    (net (code "155") (name "unconnected-(U6B-GP_Out_D3-PadB6)") (class "Default")
      (node (ref "U6") (pin "B6") (pinfunction "GP_Out_D3_B6") (pintype "passive"))
    )
    (net (code "156") (name "unconnected-(U6B-GP_Out_D4-PadB10)") (class "Default")
      (node (ref "U6") (pin "B10") (pinfunction "GP_Out_D4_B10") (pintype "passive"))
    )
    (net (code "157") (name "unconnected-(U6B-GP_Out_D5-PadB14)") (class "Default")
      (node (ref "U6") (pin "B14") (pinfunction "GP_Out_D5_B14") (pintype "passive"))
    )
    (net (code "158") (name "unconnected-(U6B-GP_Out_D6-PadB18)") (class "Default")
      (node (ref "U6") (pin "B18") (pinfunction "GP_Out_D6_B18") (pintype "passive"))
    )
    (net (code "159") (name "unconnected-(U6B-GP_Out_D7-PadB22)") (class "Default")
      (node (ref "U6") (pin "B22") (pinfunction "GP_Out_D7_B22") (pintype "passive"))
    )
    (net (code "160") (name "unconnected-(U6B-GP_Out_D8-PadB26)") (class "Default")
      (node (ref "U6") (pin "B26") (pinfunction "GP_Out_D8_B26") (pintype "passive"))
    )
    (net (code "161") (name "unconnected-(U6B-GP_Out_D9-PadB30)") (class "Default")
      (node (ref "U6") (pin "B30") (pinfunction "GP_Out_D9_B30") (pintype "passive"))
    )
    (net (code "162") (name "unconnected-(U6B-GP_Out_D10-PadB34)") (class "Default")
      (node (ref "U6") (pin "B34") (pinfunction "GP_Out_D10_B34") (pintype "passive"))
    )
    (net (code "163") (name "unconnected-(U6B-GP_Out_D11-PadB38)") (class "Default")
      (node (ref "U6") (pin "B38") (pinfunction "GP_Out_D11_B38") (pintype "passive"))
    )
    (net (code "164") (name "unconnected-(U6B-GP_Out_D12-PadB42)") (class "Default")
      (node (ref "U6") (pin "B42") (pinfunction "GP_Out_D12_B42") (pintype "passive"))
    )
    (net (code "165") (name "unconnected-(U6B-GP_Out_D13-PadB46)") (class "Default")
      (node (ref "U6") (pin "B46") (pinfunction "GP_Out_D13_B46") (pintype "passive"))
    )
    (net (code "166") (name "unconnected-(U6B-GP_Out_D14-PadB50)") (class "Default")
      (node (ref "U6") (pin "B50") (pinfunction "GP_Out_D14_B50") (pintype "passive"))
    )
    (net (code "167") (name "unconnected-(U6B-GP_Out_D15-PadB54)") (class "Default")
      (node (ref "U6") (pin "B54") (pinfunction "GP_Out_D15_B54") (pintype "passive"))
    )
    (net (code "168") (name "unconnected-(U6B-GP_Out_D16-PadB58)") (class "Default")
      (node (ref "U6") (pin "B58") (pinfunction "GP_Out_D16_B58") (pintype "passive"))
    )
    (net (code "169") (name "unconnected-(U6B-GP_Out_D17-PadB62)") (class "Default")
      (node (ref "U6") (pin "B62") (pinfunction "GP_Out_D17_B62") (pintype "passive"))
    )
    (net (code "170") (name "unconnected-(U6B-GP_Out_D18-PadB66)") (class "Default")
      (node (ref "U6") (pin "B66") (pinfunction "GP_Out_D18_B66") (pintype "passive"))
    )
    (net (code "171") (name "unconnected-(U6B-GP_Out_D19-PadB70)") (class "Default")
      (node (ref "U6") (pin "B70") (pinfunction "GP_Out_D19_B70") (pintype "passive"))
    )
    (net (code "172") (name "unconnected-(U6B-GP_Out_D20-PadB74)") (class "Default")
      (node (ref "U6") (pin "B74") (pinfunction "GP_Out_D20_B74") (pintype "passive"))
    )
    (net (code "173") (name "unconnected-(U6B-GP_Out_D21-PadB78)") (class "Default")
      (node (ref "U6") (pin "B78") (pinfunction "GP_Out_D21_B78") (pintype "passive"))
    )
    (net (code "174") (name "unconnected-(U6B-GP_Out_D22-PadB82)") (class "Default")
      (node (ref "U6") (pin "B82") (pinfunction "GP_Out_D22_B82") (pintype "passive"))
    )
    (net (code "175") (name "unconnected-(U6B-GP_Out_D23-PadB86)") (class "Default")
      (node (ref "U6") (pin "B86") (pinfunction "GP_Out_D23_B86") (pintype "passive"))
    )
    (net (code "176") (name "unconnected-(U6B-GP_Out_D24-PadB90)") (class "Default")
      (node (ref "U6") (pin "B90") (pinfunction "GP_Out_D24_B90") (pintype "passive"))
    )
    (net (code "177") (name "unconnected-(U6B-GP_Out_D25-PadB94)") (class "Default")
      (node (ref "U6") (pin "B94") (pinfunction "GP_Out_D25_B94") (pintype "passive"))
    )
    (net (code "178") (name "unconnected-(U6B-GP_Out_D26-PadB98)") (class "Default")
      (node (ref "U6") (pin "B98") (pinfunction "GP_Out_D26_B98") (pintype "passive"))
    )
    (net (code "179") (name "unconnected-(U6B-GP_Out_D27-PadB102)") (class "Default")
      (node (ref "U6") (pin "B102") (pinfunction "GP_Out_D27_B102") (pintype "passive"))
    )
    (net (code "180") (name "unconnected-(U6B-GP_Out_D28-PadB106)") (class "Default")
      (node (ref "U6") (pin "B106") (pinfunction "GP_Out_D28_B106") (pintype "passive"))
    )
    (net (code "181") (name "unconnected-(U6B-GP_Out_D29-PadB110)") (class "Default")
      (node (ref "U6") (pin "B110") (pinfunction "GP_Out_D29_B110") (pintype "passive"))
    )
    (net (code "182") (name "unconnected-(U6B-GP_Out_D30-PadB114)") (class "Default")
      (node (ref "U6") (pin "B114") (pinfunction "GP_Out_D30_B114") (pintype "passive"))
    )
    (net (code "183") (name "unconnected-(U6B-GP_Out_D31-PadB118)") (class "Default")
      (node (ref "U6") (pin "B118") (pinfunction "GP_Out_D31_B118") (pintype "passive"))
    )
    (net (code "184") (name "unconnected-(U6B-GP_Out_S0-PadB49)") (class "Default")
      (node (ref "U6") (pin "B49") (pinfunction "GP_Out_S0_B49") (pintype "passive"))
    )
    (net (code "185") (name "unconnected-(U6B-GP_Out_S1-PadB53)") (class "Default")
      (node (ref "U6") (pin "B53") (pinfunction "GP_Out_S1_B53") (pintype "passive"))
    )
    (net (code "186") (name "unconnected-(U6B-GP_Out_S2-PadB4)") (class "Default")
      (node (ref "U6") (pin "B4") (pinfunction "GP_Out_S2_B4") (pintype "passive"))
    )
    (net (code "187") (name "unconnected-(U6B-GP_Out_S3-PadB8)") (class "Default")
      (node (ref "U6") (pin "B8") (pinfunction "GP_Out_S3_B8") (pintype "passive"))
    )
    (net (code "188") (name "unconnected-(U6B-GP_Out_S4-PadB12)") (class "Default")
      (node (ref "U6") (pin "B12") (pinfunction "GP_Out_S4_B12") (pintype "passive"))
    )
    (net (code "189") (name "unconnected-(U6B-GP_Out_S5-PadB16)") (class "Default")
      (node (ref "U6") (pin "B16") (pinfunction "GP_Out_S5_B16") (pintype "passive"))
    )
    (net (code "190") (name "unconnected-(U6B-GP_Out_S6-PadB20)") (class "Default")
      (node (ref "U6") (pin "B20") (pinfunction "GP_Out_S6_B20") (pintype "passive"))
    )
    (net (code "191") (name "unconnected-(U6B-GP_Out_S7-PadB24)") (class "Default")
      (node (ref "U6") (pin "B24") (pinfunction "GP_Out_S7_B24") (pintype "passive"))
    )
    (net (code "192") (name "unconnected-(U6B-GP_Out_S8-PadB28)") (class "Default")
      (node (ref "U6") (pin "B28") (pinfunction "GP_Out_S8_B28") (pintype "passive"))
    )
    (net (code "193") (name "unconnected-(U6B-GP_Out_S9-PadB32)") (class "Default")
      (node (ref "U6") (pin "B32") (pinfunction "GP_Out_S9_B32") (pintype "passive"))
    )
    (net (code "194") (name "unconnected-(U6B-GP_Out_S10-PadB36)") (class "Default")
      (node (ref "U6") (pin "B36") (pinfunction "GP_Out_S10_B36") (pintype "passive"))
    )
    (net (code "195") (name "unconnected-(U6B-GP_Out_S11-PadB40)") (class "Default")
      (node (ref "U6") (pin "B40") (pinfunction "GP_Out_S11_B40") (pintype "passive"))
    )
    (net (code "196") (name "unconnected-(U6B-GP_Out_S12-PadB44)") (class "Default")
      (node (ref "U6") (pin "B44") (pinfunction "GP_Out_S12_B44") (pintype "passive"))
    )
    (net (code "197") (name "unconnected-(U6B-GP_Out_S13-PadB48)") (class "Default")
      (node (ref "U6") (pin "B48") (pinfunction "GP_Out_S13_B48") (pintype "passive"))
    )
    (net (code "198") (name "unconnected-(U6B-GP_Out_S14-PadB52)") (class "Default")
      (node (ref "U6") (pin "B52") (pinfunction "GP_Out_S14_B52") (pintype "passive"))
    )
    (net (code "199") (name "unconnected-(U6B-GP_Out_S15-PadB56)") (class "Default")
      (node (ref "U6") (pin "B56") (pinfunction "GP_Out_S15_B56") (pintype "passive"))
    )
    (net (code "200") (name "unconnected-(U6B-GP_Out_S16-PadB60)") (class "Default")
      (node (ref "U6") (pin "B60") (pinfunction "GP_Out_S16_B60") (pintype "passive"))
    )
    (net (code "201") (name "unconnected-(U6B-GP_Out_S17-PadB64)") (class "Default")
      (node (ref "U6") (pin "B64") (pinfunction "GP_Out_S17_B64") (pintype "passive"))
    )
    (net (code "202") (name "unconnected-(U6B-GP_Out_S18-PadB68)") (class "Default")
      (node (ref "U6") (pin "B68") (pinfunction "GP_Out_S18_B68") (pintype "passive"))
    )
    (net (code "203") (name "unconnected-(U6B-GP_Out_S19-PadB72)") (class "Default")
      (node (ref "U6") (pin "B72") (pinfunction "GP_Out_S19_B72") (pintype "passive"))
    )
    (net (code "204") (name "unconnected-(U6B-GP_Out_S20-PadB76)") (class "Default")
      (node (ref "U6") (pin "B76") (pinfunction "GP_Out_S20_B76") (pintype "passive"))
    )
    (net (code "205") (name "unconnected-(U6B-GP_Out_S21-PadB80)") (class "Default")
      (node (ref "U6") (pin "B80") (pinfunction "GP_Out_S21_B80") (pintype "passive"))
    )
    (net (code "206") (name "unconnected-(U6B-GP_Out_S22-PadB84)") (class "Default")
      (node (ref "U6") (pin "B84") (pinfunction "GP_Out_S22_B84") (pintype "passive"))
    )
    (net (code "207") (name "unconnected-(U6B-GP_Out_S23-PadB88)") (class "Default")
      (node (ref "U6") (pin "B88") (pinfunction "GP_Out_S23_B88") (pintype "passive"))
    )
    (net (code "208") (name "unconnected-(U6B-GP_Out_S24-PadB92)") (class "Default")
      (node (ref "U6") (pin "B92") (pinfunction "GP_Out_S24_B92") (pintype "passive"))
    )
    (net (code "209") (name "unconnected-(U6B-GP_Out_S25-PadB96)") (class "Default")
      (node (ref "U6") (pin "B96") (pinfunction "GP_Out_S25_B96") (pintype "passive"))
    )
    (net (code "210") (name "unconnected-(U6B-GP_Out_S26-PadB100)") (class "Default")
      (node (ref "U6") (pin "B100") (pinfunction "GP_Out_S26_B100") (pintype "passive"))
    )
    (net (code "211") (name "unconnected-(U6B-GP_Out_S27-PadB104)") (class "Default")
      (node (ref "U6") (pin "B104") (pinfunction "GP_Out_S27_B104") (pintype "passive"))
    )
    (net (code "212") (name "unconnected-(U6B-GP_Out_S28-PadB108)") (class "Default")
      (node (ref "U6") (pin "B108") (pinfunction "GP_Out_S28_B108") (pintype "passive"))
    )
    (net (code "213") (name "unconnected-(U6B-GP_Out_S29-PadB112)") (class "Default")
      (node (ref "U6") (pin "B112") (pinfunction "GP_Out_S29_B112") (pintype "passive"))
    )
    (net (code "214") (name "unconnected-(U6B-GP_Out_S30-PadB116)") (class "Default")
      (node (ref "U6") (pin "B116") (pinfunction "GP_Out_S30_B116") (pintype "passive"))
    )
    (net (code "215") (name "unconnected-(U6B-GP_Out_S31-PadB120)") (class "Default")
      (node (ref "U6") (pin "B120") (pinfunction "GP_Out_S31_B120") (pintype "passive"))
    )
    (net (code "216") (name "unconnected-(U6B-HomeCom-PadB9)") (class "Default")
      (node (ref "U6") (pin "B9") (pinfunction "HomeCom_B9") (pintype "passive"))
    )
    (net (code "217") (name "unconnected-(U6B-NegLimt1-PadB27)") (class "Default")
      (node (ref "U6") (pin "B27") (pinfunction "NegLimt1_B27") (pintype "passive"))
    )
    (net (code "218") (name "unconnected-(U6B-NegLimt2-PadB25)") (class "Default")
      (node (ref "U6") (pin "B25") (pinfunction "NegLimt2_B25") (pintype "passive"))
    )
    (net (code "219") (name "unconnected-(U6B-NegLimt3-PadB23)") (class "Default")
      (node (ref "U6") (pin "B23") (pinfunction "NegLimt3_B23") (pintype "passive"))
    )
    (net (code "220") (name "unconnected-(U6B-NegLimt4-PadB21)") (class "Default")
      (node (ref "U6") (pin "B21") (pinfunction "NegLimt4_B21") (pintype "passive"))
    )
    (net (code "221") (name "unconnected-(U6B-NegLimtCom-PadB29)") (class "Default")
      (node (ref "U6") (pin "B29") (pinfunction "NegLimtCom_B29") (pintype "passive"))
    )
    (net (code "222") (name "unconnected-(U6B-Opto_Input4-PadB73)") (class "Default")
      (node (ref "U6") (pin "B73") (pinfunction "Opto_Input4_B73") (pintype "passive"))
    )
    (net (code "223") (name "unconnected-(U6B-Opto_Input5-PadB75)") (class "Default")
      (node (ref "U6") (pin "B75") (pinfunction "Opto_Input5_B75") (pintype "passive"))
    )
    (net (code "224") (name "unconnected-(U6B-Opto_Input6-PadB77)") (class "Default")
      (node (ref "U6") (pin "B77") (pinfunction "Opto_Input6_B77") (pintype "passive"))
    )
    (net (code "225") (name "unconnected-(U6B-Opto_Input7-PadB79)") (class "Default")
      (node (ref "U6") (pin "B79") (pinfunction "Opto_Input7_B79") (pintype "passive"))
    )
    (net (code "226") (name "unconnected-(U6B-Opto_Input8-PadB83)") (class "Default")
      (node (ref "U6") (pin "B83") (pinfunction "Opto_Input8_B83") (pintype "passive"))
    )
    (net (code "227") (name "unconnected-(U6B-Opto_Input9-PadB85)") (class "Default")
      (node (ref "U6") (pin "B85") (pinfunction "Opto_Input9_B85") (pintype "passive"))
    )
    (net (code "228") (name "unconnected-(U6B-Opto_Input10-PadB87)") (class "Default")
      (node (ref "U6") (pin "B87") (pinfunction "Opto_Input10_B87") (pintype "passive"))
    )
    (net (code "229") (name "unconnected-(U6B-Opto_Input11-PadB89)") (class "Default")
      (node (ref "U6") (pin "B89") (pinfunction "Opto_Input11_B89") (pintype "passive"))
    )
    (net (code "230") (name "unconnected-(U6B-Opto_Input12-PadB93)") (class "Default")
      (node (ref "U6") (pin "B93") (pinfunction "Opto_Input12_B93") (pintype "passive"))
    )
    (net (code "231") (name "unconnected-(U6B-Opto_Input13-PadB95)") (class "Default")
      (node (ref "U6") (pin "B95") (pinfunction "Opto_Input13_B95") (pintype "passive"))
    )
    (net (code "232") (name "unconnected-(U6B-Opto_Input14-PadB97)") (class "Default")
      (node (ref "U6") (pin "B97") (pinfunction "Opto_Input14_B97") (pintype "passive"))
    )
    (net (code "233") (name "unconnected-(U6B-Opto_Input15-PadB99)") (class "Default")
      (node (ref "U6") (pin "B99") (pinfunction "Opto_Input15_B99") (pintype "passive"))
    )
    (net (code "234") (name "unconnected-(U6B-Opto_Input16-PadB103)") (class "Default")
      (node (ref "U6") (pin "B103") (pinfunction "Opto_Input16_B103") (pintype "passive"))
    )
    (net (code "235") (name "unconnected-(U6B-Opto_Input17-PadB105)") (class "Default")
      (node (ref "U6") (pin "B105") (pinfunction "Opto_Input17_B105") (pintype "passive"))
    )
    (net (code "236") (name "unconnected-(U6B-Opto_Input18-PadB107)") (class "Default")
      (node (ref "U6") (pin "B107") (pinfunction "Opto_Input18_B107") (pintype "passive"))
    )
    (net (code "237") (name "unconnected-(U6B-Opto_Input19-PadB109)") (class "Default")
      (node (ref "U6") (pin "B109") (pinfunction "Opto_Input19_B109") (pintype "passive"))
    )
    (net (code "238") (name "unconnected-(U6B-Opto_Input20-PadB113)") (class "Default")
      (node (ref "U6") (pin "B113") (pinfunction "Opto_Input20_B113") (pintype "passive"))
    )
    (net (code "239") (name "unconnected-(U6B-Opto_Input21-PadB115)") (class "Default")
      (node (ref "U6") (pin "B115") (pinfunction "Opto_Input21_B115") (pintype "passive"))
    )
    (net (code "240") (name "unconnected-(U6B-Opto_Input22-PadB117)") (class "Default")
      (node (ref "U6") (pin "B117") (pinfunction "Opto_Input22_B117") (pintype "passive"))
    )
    (net (code "241") (name "unconnected-(U6B-Opto_Input23-PadB119)") (class "Default")
      (node (ref "U6") (pin "B119") (pinfunction "Opto_Input23_B119") (pintype "passive"))
    )
    (net (code "242") (name "unconnected-(U6B-Opto_Input_Com1-PadB71)") (class "Default")
      (node (ref "U6") (pin "B71") (pinfunction "Opto_Input_Com1_B71") (pintype "passive"))
    )
    (net (code "243") (name "unconnected-(U6B-Opto_Input_Com2-PadB81)") (class "Default")
      (node (ref "U6") (pin "B81") (pinfunction "Opto_Input_Com2_B81") (pintype "passive"))
    )
    (net (code "244") (name "unconnected-(U6B-Opto_Input_Com3-PadB91)") (class "Default")
      (node (ref "U6") (pin "B91") (pinfunction "Opto_Input_Com3_B91") (pintype "passive"))
    )
    (net (code "245") (name "unconnected-(U6B-Opto_Input_Com4-PadB101)") (class "Default")
      (node (ref "U6") (pin "B101") (pinfunction "Opto_Input_Com4_B101") (pintype "passive"))
    )
    (net (code "246") (name "unconnected-(U6B-Opto_Input_Com5-PadB111)") (class "Default")
      (node (ref "U6") (pin "B111") (pinfunction "Opto_Input_Com5_B111") (pintype "passive"))
    )
    (net (code "247") (name "unconnected-(U6B-PosLimt1-PadB17)") (class "Default")
      (node (ref "U6") (pin "B17") (pinfunction "PosLimt1_B17") (pintype "passive"))
    )
    (net (code "248") (name "unconnected-(U6B-PosLimt2-PadB15)") (class "Default")
      (node (ref "U6") (pin "B15") (pinfunction "PosLimt2_B15") (pintype "passive"))
    )
    (net (code "249") (name "unconnected-(U6B-PosLimt3-PadB13)") (class "Default")
      (node (ref "U6") (pin "B13") (pinfunction "PosLimt3_B13") (pintype "passive"))
    )
    (net (code "250") (name "unconnected-(U6B-PosLimt4-PadB11)") (class "Default")
      (node (ref "U6") (pin "B11") (pinfunction "PosLimt4_B11") (pintype "passive"))
    )
    (net (code "251") (name "unconnected-(U6B-PosLimtCom-PadB19)") (class "Default")
      (node (ref "U6") (pin "B19") (pinfunction "PosLimtCom_B19") (pintype "passive"))
    )
    (net (code "252") (name "unconnected-(U6B-Step1-PadB31)") (class "Default")
      (node (ref "U6") (pin "B31") (pinfunction "Step1_B31") (pintype "passive"))
    )
    (net (code "253") (name "unconnected-(U6B-Step2-PadB33)") (class "Default")
      (node (ref "U6") (pin "B33") (pinfunction "Step2_B33") (pintype "passive"))
    )
    (net (code "254") (name "unconnected-(U6B-Step3-PadB35)") (class "Default")
      (node (ref "U6") (pin "B35") (pinfunction "Step3_B35") (pintype "passive"))
    )
    (net (code "255") (name "unconnected-(U6B-Step4-PadB37)") (class "Default")
      (node (ref "U6") (pin "B37") (pinfunction "Step4_B37") (pintype "passive"))
    )
    (net (code "256") (name "unconnected-(U6B-~Home1-PadB7)") (class "Default")
      (node (ref "U6") (pin "B7") (pinfunction "~Home1_B7") (pintype "passive"))
    )
    (net (code "257") (name "unconnected-(U6B-~Home2-PadB5)") (class "Default")
      (node (ref "U6") (pin "B5") (pinfunction "~Home2_B5") (pintype "passive"))
    )
    (net (code "258") (name "unconnected-(U6B-~Home3-PadB3)") (class "Default")
      (node (ref "U6") (pin "B3") (pinfunction "~Home3_B3") (pintype "passive"))
    )
    (net (code "259") (name "unconnected-(U6B-~Home4-PadB1)") (class "Default")
      (node (ref "U6") (pin "B1") (pinfunction "~Home4_B1") (pintype "passive"))
    )
  )
)
